# 09_LEDs_2.net
KiCad netlist of a schematic drawn in Altium Designer
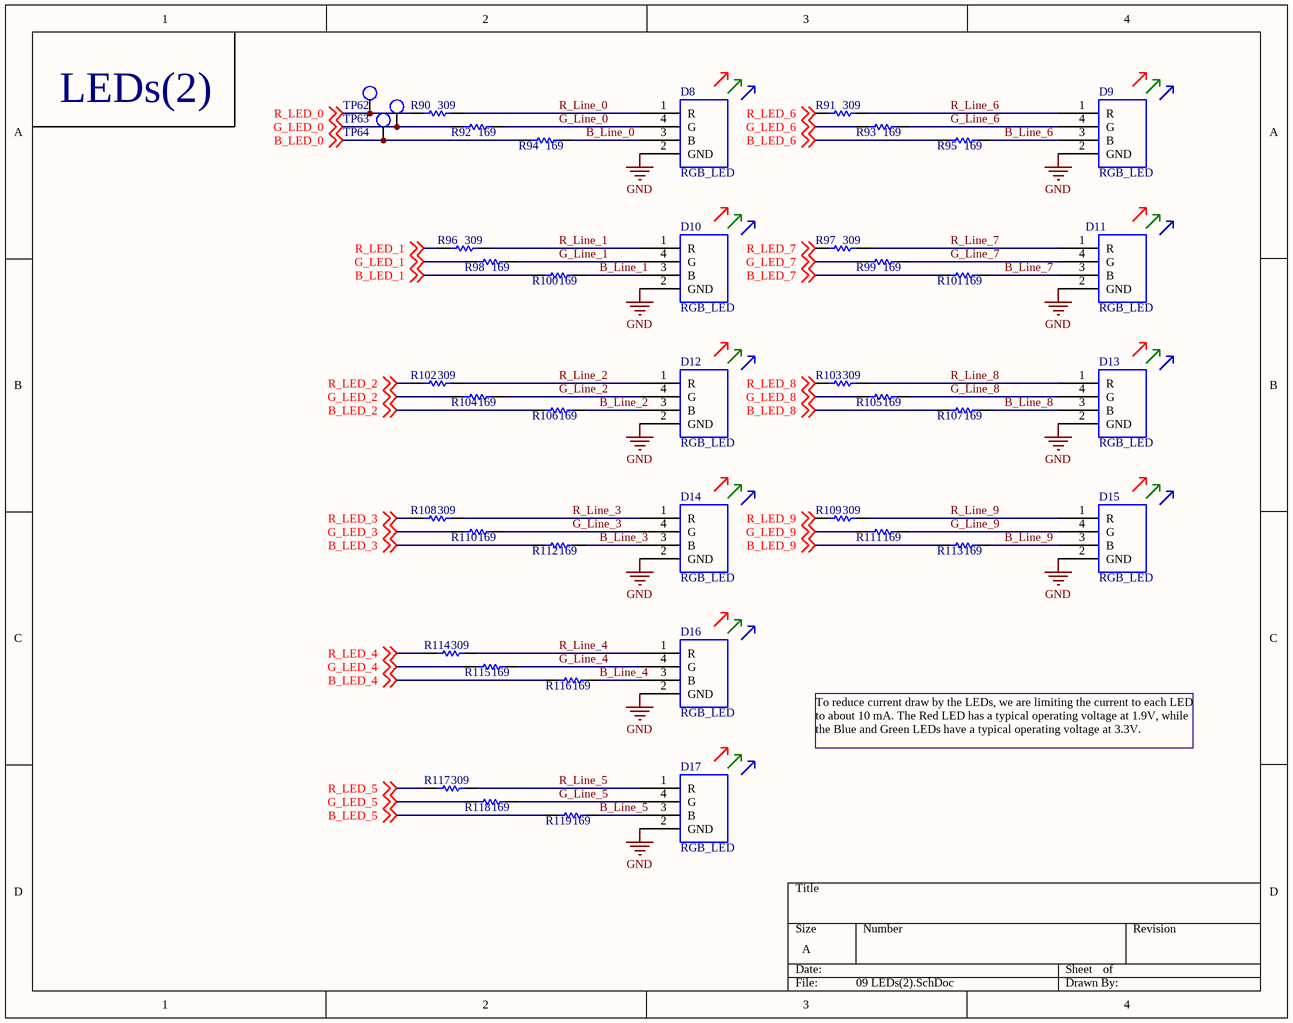
[diagram p0: 09 LEDs(2).SchDoc]

(export (version "E")
  (design (tool "Eeschema 10.0.6"))
  (components
    (comp (ref "D8")
      (value "RGB_LED")
      (footprint "RGB_LED")
      (description "WP154A4SUREQBFZGC")
      (fields (field (name "MANUFACTURER") "Kingbright"))
      (libsource (lib "schlib_truman") (part "RGB_LED"))
    )
    (comp (ref "D9")
      (value "RGB_LED")
      (footprint "RGB_LED")
      (description "WP154A4SUREQBFZGC")
      (fields (field (name "MANUFACTURER") "Kingbright"))
      (libsource (lib "schlib_truman") (part "RGB_LED"))
    )
    (comp (ref "D10")
      (value "RGB_LED")
      (footprint "RGB_LED")
      (description "WP154A4SUREQBFZGC")
      (fields (field (name "MANUFACTURER") "Kingbright"))
      (libsource (lib "schlib_truman") (part "RGB_LED"))
    )
    (comp (ref "D11")
      (value "RGB_LED")
      (footprint "RGB_LED")
      (description "WP154A4SUREQBFZGC")
      (fields (field (name "MANUFACTURER") "Kingbright"))
      (libsource (lib "schlib_truman") (part "RGB_LED"))
    )
    (comp (ref "D12")
      (value "RGB_LED")
      (footprint "RGB_LED")
      (description "WP154A4SUREQBFZGC")
      (fields (field (name "MANUFACTURER") "Kingbright"))
      (libsource (lib "schlib_truman") (part "RGB_LED"))
    )
    (comp (ref "D13")
      (value "RGB_LED")
      (footprint "RGB_LED")
      (description "WP154A4SUREQBFZGC")
      (fields (field (name "MANUFACTURER") "Kingbright"))
      (libsource (lib "schlib_truman") (part "RGB_LED"))
    )
    (comp (ref "D14")
      (value "RGB_LED")
      (footprint "RGB_LED")
      (description "WP154A4SUREQBFZGC")
      (fields (field (name "MANUFACTURER") "Kingbright"))
      (libsource (lib "schlib_truman") (part "RGB_LED"))
    )
    (comp (ref "D15")
      (value "RGB_LED")
      (footprint "RGB_LED")
      (description "WP154A4SUREQBFZGC")
      (fields (field (name "MANUFACTURER") "Kingbright"))
      (libsource (lib "schlib_truman") (part "RGB_LED"))
    )
    (comp (ref "D16")
      (value "RGB_LED")
      (footprint "RGB_LED")
      (description "WP154A4SUREQBFZGC")
      (fields (field (name "MANUFACTURER") "Kingbright"))
      (libsource (lib "schlib_truman") (part "RGB_LED"))
    )
    (comp (ref "D17")
      (value "RGB_LED")
      (footprint "RGB_LED")
      (description "WP154A4SUREQBFZGC")
      (fields (field (name "MANUFACTURER") "Kingbright"))
      (libsource (lib "schlib_truman") (part "RGB_LED"))
    )
    (comp (ref "R90")
      (value "RES_0805_309")
      (footprint "RES0805")
      (description "RES SMD 309 OHM 1% 1/8W 0805")
      (fields
        (field (name "MANUFACTURER") "Yageo")
        (field (name "MANUFACTURER PART NUMBER") "RC0805FR-07309RL")
        (field (name "ALTIUM_UNNAMED_1") "309")
      )
      (libsource (lib "schlib_truman") (part "RES_0805_309"))
    )
    (comp (ref "R91")
      (value "RES_0805_309")
      (footprint "RES0805")
      (description "RES SMD 309 OHM 1% 1/8W 0805")
      (fields
        (field (name "MANUFACTURER") "Yageo")
        (field (name "MANUFACTURER PART NUMBER") "RC0805FR-07309RL")
        (field (name "ALTIUM_UNNAMED_1") "309")
      )
      (libsource (lib "schlib_truman") (part "RES_0805_309"))
    )
    (comp (ref "R92")
      (value "169 Ohm")
      (footprint "RES0805")
      (description "RES SMD 169 OHM 1% 1/8W 0805")
      (fields
        (field (name "MANUFACTURER") "Yageo")
        (field (name "MANUFACTURER PART NUMBER") "RC0805FR-07169RL")
        (field (name "ALTIUM_UNNAMED_1") "169")
      )
      (libsource (lib "schlib_truman") (part "RES_0805_169"))
    )
    (comp (ref "R93")
      (value "169 Ohm")
      (footprint "RES0805")
      (description "RES SMD 169 OHM 1% 1/8W 0805")
      (fields
        (field (name "MANUFACTURER") "Yageo")
        (field (name "MANUFACTURER PART NUMBER") "RC0805FR-07169RL")
        (field (name "ALTIUM_UNNAMED_1") "169")
      )
      (libsource (lib "schlib_truman") (part "RES_0805_169"))
    )
    (comp (ref "R94")
      (value "169 Ohm")
      (footprint "RES0805")
      (description "RES SMD 169 OHM 1% 1/8W 0805")
      (fields
        (field (name "MANUFACTURER") "Yageo")
        (field (name "MANUFACTURER PART NUMBER") "RC0805FR-07169RL")
        (field (name "ALTIUM_UNNAMED_1") "169")
      )
      (libsource (lib "schlib_truman") (part "RES_0805_169"))
    )
    (comp (ref "R95")
      (value "169 Ohm")
      (footprint "RES0805")
      (description "RES SMD 169 OHM 1% 1/8W 0805")
      (fields
        (field (name "MANUFACTURER") "Yageo")
        (field (name "MANUFACTURER PART NUMBER") "RC0805FR-07169RL")
        (field (name "ALTIUM_UNNAMED_1") "169")
      )
      (libsource (lib "schlib_truman") (part "RES_0805_169"))
    )
    (comp (ref "R96")
      (value "RES_0805_309")
      (footprint "RES0805")
      (description "RES SMD 309 OHM 1% 1/8W 0805")
      (fields
        (field (name "MANUFACTURER") "Yageo")
        (field (name "MANUFACTURER PART NUMBER") "RC0805FR-07309RL")
        (field (name "ALTIUM_UNNAMED_1") "309")
      )
      (libsource (lib "schlib_truman") (part "RES_0805_309"))
    )
    (comp (ref "R97")
      (value "RES_0805_309")
      (footprint "RES0805")
      (description "RES SMD 309 OHM 1% 1/8W 0805")
      (fields
        (field (name "MANUFACTURER") "Yageo")
        (field (name "MANUFACTURER PART NUMBER") "RC0805FR-07309RL")
        (field (name "ALTIUM_UNNAMED_1") "309")
      )
      (libsource (lib "schlib_truman") (part "RES_0805_309"))
    )
    (comp (ref "R98")
      (value "169 Ohm")
      (footprint "RES0805")
      (description "RES SMD 169 OHM 1% 1/8W 0805")
      (fields
        (field (name "MANUFACTURER") "Yageo")
        (field (name "MANUFACTURER PART NUMBER") "RC0805FR-07169RL")
        (field (name "ALTIUM_UNNAMED_1") "169")
      )
      (libsource (lib "schlib_truman") (part "RES_0805_169"))
    )
    (comp (ref "R99")
      (value "169 Ohm")
      (footprint "RES0805")
      (description "RES SMD 169 OHM 1% 1/8W 0805")
      (fields
        (field (name "MANUFACTURER") "Yageo")
        (field (name "MANUFACTURER PART NUMBER") "RC0805FR-07169RL")
        (field (name "ALTIUM_UNNAMED_1") "169")
      )
      (libsource (lib "schlib_truman") (part "RES_0805_169"))
    )
    (comp (ref "R100")
      (value "169 Ohm")
      (footprint "RES0805")
      (description "RES SMD 169 OHM 1% 1/8W 0805")
      (fields
        (field (name "MANUFACTURER") "Yageo")
        (field (name "MANUFACTURER PART NUMBER") "RC0805FR-07169RL")
        (field (name "ALTIUM_UNNAMED_1") "169")
      )
      (libsource (lib "schlib_truman") (part "RES_0805_169"))
    )
    (comp (ref "R101")
      (value "169 Ohm")
      (footprint "RES0805")
      (description "RES SMD 169 OHM 1% 1/8W 0805")
      (fields
        (field (name "MANUFACTURER") "Yageo")
        (field (name "MANUFACTURER PART NUMBER") "RC0805FR-07169RL")
        (field (name "ALTIUM_UNNAMED_1") "169")
      )
      (libsource (lib "schlib_truman") (part "RES_0805_169"))
    )
    (comp (ref "R102")
      (value "RES_0805_309")
      (footprint "RES0805")
      (description "RES SMD 309 OHM 1% 1/8W 0805")
      (fields
        (field (name "MANUFACTURER") "Yageo")
        (field (name "MANUFACTURER PART NUMBER") "RC0805FR-07309RL")
        (field (name "ALTIUM_UNNAMED_1") "309")
      )
      (libsource (lib "schlib_truman") (part "RES_0805_309"))
    )
    (comp (ref "R103")
      (value "RES_0805_309")
      (footprint "RES0805")
      (description "RES SMD 309 OHM 1% 1/8W 0805")
      (fields
        (field (name "MANUFACTURER") "Yageo")
        (field (name "MANUFACTURER PART NUMBER") "RC0805FR-07309RL")
        (field (name "ALTIUM_UNNAMED_1") "309")
      )
      (libsource (lib "schlib_truman") (part "RES_0805_309"))
    )
    (comp (ref "R104")
      (value "169 Ohm")
      (footprint "RES0805")
      (description "RES SMD 169 OHM 1% 1/8W 0805")
      (fields
        (field (name "MANUFACTURER") "Yageo")
        (field (name "MANUFACTURER PART NUMBER") "RC0805FR-07169RL")
        (field (name "ALTIUM_UNNAMED_1") "169")
      )
      (libsource (lib "schlib_truman") (part "RES_0805_169"))
    )
    (comp (ref "R105")
      (value "169 Ohm")
      (footprint "RES0805")
      (description "RES SMD 169 OHM 1% 1/8W 0805")
      (fields
        (field (name "MANUFACTURER") "Yageo")
        (field (name "MANUFACTURER PART NUMBER") "RC0805FR-07169RL")
        (field (name "ALTIUM_UNNAMED_1") "169")
      )
      (libsource (lib "schlib_truman") (part "RES_0805_169"))
    )
    (comp (ref "R106")
      (value "169 Ohm")
      (footprint "RES0805")
      (description "RES SMD 169 OHM 1% 1/8W 0805")
      (fields
        (field (name "MANUFACTURER") "Yageo")
        (field (name "MANUFACTURER PART NUMBER") "RC0805FR-07169RL")
        (field (name "ALTIUM_UNNAMED_1") "169")
      )
      (libsource (lib "schlib_truman") (part "RES_0805_169"))
    )
    (comp (ref "R107")
      (value "169 Ohm")
      (footprint "RES0805")
      (description "RES SMD 169 OHM 1% 1/8W 0805")
      (fields
        (field (name "MANUFACTURER") "Yageo")
        (field (name "MANUFACTURER PART NUMBER") "RC0805FR-07169RL")
        (field (name "ALTIUM_UNNAMED_1") "169")
      )
      (libsource (lib "schlib_truman") (part "RES_0805_169"))
    )
    (comp (ref "R108")
      (value "RES_0805_309")
      (footprint "RES0805")
      (description "RES SMD 309 OHM 1% 1/8W 0805")
      (fields
        (field (name "MANUFACTURER") "Yageo")
        (field (name "MANUFACTURER PART NUMBER") "RC0805FR-07309RL")
        (field (name "ALTIUM_UNNAMED_1") "309")
      )
      (libsource (lib "schlib_truman") (part "RES_0805_309"))
    )
    (comp (ref "R109")
      (value "RES_0805_309")
      (footprint "RES0805")
      (description "RES SMD 309 OHM 1% 1/8W 0805")
      (fields
        (field (name "MANUFACTURER") "Yageo")
        (field (name "MANUFACTURER PART NUMBER") "RC0805FR-07309RL")
        (field (name "ALTIUM_UNNAMED_1") "309")
      )
      (libsource (lib "schlib_truman") (part "RES_0805_309"))
    )
    (comp (ref "R110")
      (value "169 Ohm")
      (footprint "RES0805")
      (description "RES SMD 169 OHM 1% 1/8W 0805")
      (fields
        (field (name "MANUFACTURER") "Yageo")
        (field (name "MANUFACTURER PART NUMBER") "RC0805FR-07169RL")
        (field (name "ALTIUM_UNNAMED_1") "169")
      )
      (libsource (lib "schlib_truman") (part "RES_0805_169"))
    )
    (comp (ref "R111")
      (value "169 Ohm")
      (footprint "RES0805")
      (description "RES SMD 169 OHM 1% 1/8W 0805")
      (fields
        (field (name "MANUFACTURER") "Yageo")
        (field (name "MANUFACTURER PART NUMBER") "RC0805FR-07169RL")
        (field (name "ALTIUM_UNNAMED_1") "169")
      )
      (libsource (lib "schlib_truman") (part "RES_0805_169"))
    )
    (comp (ref "R112")
      (value "169 Ohm")
      (footprint "RES0805")
      (description "RES SMD 169 OHM 1% 1/8W 0805")
      (fields
        (field (name "MANUFACTURER") "Yageo")
        (field (name "MANUFACTURER PART NUMBER") "RC0805FR-07169RL")
        (field (name "ALTIUM_UNNAMED_1") "169")
      )
      (libsource (lib "schlib_truman") (part "RES_0805_169"))
    )
    (comp (ref "R113")
      (value "169 Ohm")
      (footprint "RES0805")
      (description "RES SMD 169 OHM 1% 1/8W 0805")
      (fields
        (field (name "MANUFACTURER") "Yageo")
        (field (name "MANUFACTURER PART NUMBER") "RC0805FR-07169RL")
        (field (name "ALTIUM_UNNAMED_1") "169")
      )
      (libsource (lib "schlib_truman") (part "RES_0805_169"))
    )
    (comp (ref "R114")
      (value "RES_0805_309")
      (footprint "RES0805")
      (description "RES SMD 309 OHM 1% 1/8W 0805")
      (fields
        (field (name "MANUFACTURER") "Yageo")
        (field (name "MANUFACTURER PART NUMBER") "RC0805FR-07309RL")
        (field (name "ALTIUM_UNNAMED_1") "309")
      )
      (libsource (lib "schlib_truman") (part "RES_0805_309"))
    )
    (comp (ref "R115")
      (value "169 Ohm")
      (footprint "RES0805")
      (description "RES SMD 169 OHM 1% 1/8W 0805")
      (fields
        (field (name "MANUFACTURER") "Yageo")
        (field (name "MANUFACTURER PART NUMBER") "RC0805FR-07169RL")
        (field (name "ALTIUM_UNNAMED_1") "169")
      )
      (libsource (lib "schlib_truman") (part "RES_0805_169"))
    )
    (comp (ref "R116")
      (value "169 Ohm")
      (footprint "RES0805")
      (description "RES SMD 169 OHM 1% 1/8W 0805")
      (fields
        (field (name "MANUFACTURER") "Yageo")
        (field (name "MANUFACTURER PART NUMBER") "RC0805FR-07169RL")
        (field (name "ALTIUM_UNNAMED_1") "169")
      )
      (libsource (lib "schlib_truman") (part "RES_0805_169"))
    )
    (comp (ref "R117")
      (value "RES_0805_309")
      (footprint "RES0805")
      (description "RES SMD 309 OHM 1% 1/8W 0805")
      (fields
        (field (name "MANUFACTURER") "Yageo")
        (field (name "MANUFACTURER PART NUMBER") "RC0805FR-07309RL")
        (field (name "ALTIUM_UNNAMED_1") "309")
      )
      (libsource (lib "schlib_truman") (part "RES_0805_309"))
    )
    (comp (ref "R118")
      (value "169 Ohm")
      (footprint "RES0805")
      (description "RES SMD 169 OHM 1% 1/8W 0805")
      (fields
        (field (name "MANUFACTURER") "Yageo")
        (field (name "MANUFACTURER PART NUMBER") "RC0805FR-07169RL")
        (field (name "ALTIUM_UNNAMED_1") "169")
      )
      (libsource (lib "schlib_truman") (part "RES_0805_169"))
    )
    (comp (ref "R119")
      (value "169 Ohm")
      (footprint "RES0805")
      (description "RES SMD 169 OHM 1% 1/8W 0805")
      (fields
        (field (name "MANUFACTURER") "Yageo")
        (field (name "MANUFACTURER PART NUMBER") "RC0805FR-07169RL")
        (field (name "ALTIUM_UNNAMED_1") "169")
      )
      (libsource (lib "schlib_truman") (part "RES_0805_169"))
    )
    (comp (ref "TP62")
      (value "TP")
      (footprint "TestPoint_0805")
      (description "Testpoint_0805")
      (fields
        (field (name "MANUFACTURER") "TE Connectivity")
        (field (name "MANUFACTURER PART NUMBER") "1625854-2")
      )
      (libsource (lib "schlib_truman") (part "TP"))
    )
    (comp (ref "TP63")
      (value "TP")
      (footprint "TestPoint_0805")
      (description "Testpoint_0805")
      (fields
        (field (name "MANUFACTURER") "TE Connectivity")
        (field (name "MANUFACTURER PART NUMBER") "1625854-2")
      )
      (libsource (lib "schlib_truman") (part "TP"))
    )
    (comp (ref "TP64")
      (value "TP")
      (footprint "TestPoint_0805")
      (description "Testpoint_0805")
      (fields
        (field (name "MANUFACTURER") "TE Connectivity")
        (field (name "MANUFACTURER PART NUMBER") "1625854-2")
      )
      (libsource (lib "schlib_truman") (part "TP"))
    )
  )
  (nets
    (net (code "1") (name "/B_Line_0") (class "Default")
      (node (ref "D8") (pin "3") (pinfunction "B_3") (pintype "passive"))
      (node (ref "R94") (pin "2") (pinfunction "2_2") (pintype "passive"))
    )
    (net (code "2") (name "/B_Line_1") (class "Default")
      (node (ref "D10") (pin "3") (pinfunction "B_3") (pintype "passive"))
      (node (ref "R100") (pin "2") (pinfunction "2_2") (pintype "passive"))
    )
    (net (code "3") (name "/B_Line_2") (class "Default")
      (node (ref "D12") (pin "3") (pinfunction "B_3") (pintype "passive"))
      (node (ref "R106") (pin "2") (pinfunction "2_2") (pintype "passive"))
    )
    (net (code "4") (name "/B_Line_3") (class "Default")
      (node (ref "D14") (pin "3") (pinfunction "B_3") (pintype "passive"))
      (node (ref "R112") (pin "2") (pinfunction "2_2") (pintype "passive"))
    )
    (net (code "5") (name "/B_Line_4") (class "Default")
      (node (ref "D16") (pin "3") (pinfunction "B_3") (pintype "passive"))
      (node (ref "R116") (pin "2") (pinfunction "2_2") (pintype "passive"))
    )
    (net (code "6") (name "/B_Line_5") (class "Default")
      (node (ref "D17") (pin "3") (pinfunction "B_3") (pintype "passive"))
      (node (ref "R119") (pin "2") (pinfunction "2_2") (pintype "passive"))
    )
    (net (code "7") (name "/B_Line_6") (class "Default")
      (node (ref "D9") (pin "3") (pinfunction "B_3") (pintype "passive"))
      (node (ref "R95") (pin "2") (pinfunction "2_2") (pintype "passive"))
    )
    (net (code "8") (name "/B_Line_7") (class "Default")
      (node (ref "D11") (pin "3") (pinfunction "B_3") (pintype "passive"))
      (node (ref "R101") (pin "2") (pinfunction "2_2") (pintype "passive"))
    )
    (net (code "9") (name "/B_Line_8") (class "Default")
      (node (ref "D13") (pin "3") (pinfunction "B_3") (pintype "passive"))
      (node (ref "R107") (pin "2") (pinfunction "2_2") (pintype "passive"))
    )
    (net (code "10") (name "/B_Line_9") (class "Default")
      (node (ref "D15") (pin "3") (pinfunction "B_3") (pintype "passive"))
      (node (ref "R113") (pin "2") (pinfunction "2_2") (pintype "passive"))
    )
    (net (code "11") (name "/G_Line_0") (class "Default")
      (node (ref "D8") (pin "4") (pinfunction "G_4") (pintype "passive"))
      (node (ref "R92") (pin "2") (pinfunction "2_2") (pintype "passive"))
    )
    (net (code "12") (name "/G_Line_1") (class "Default")
      (node (ref "D10") (pin "4") (pinfunction "G_4") (pintype "passive"))
      (node (ref "R98") (pin "2") (pinfunction "2_2") (pintype "passive"))
    )
    (net (code "13") (name "/G_Line_2") (class "Default")
      (node (ref "D12") (pin "4") (pinfunction "G_4") (pintype "passive"))
      (node (ref "R104") (pin "2") (pinfunction "2_2") (pintype "passive"))
    )
    (net (code "14") (name "/G_Line_3") (class "Default")
      (node (ref "D14") (pin "4") (pinfunction "G_4") (pintype "passive"))
      (node (ref "R110") (pin "2") (pinfunction "2_2") (pintype "passive"))
    )
    (net (code "15") (name "/G_Line_4") (class "Default")
      (node (ref "D16") (pin "4") (pinfunction "G_4") (pintype "passive"))
      (node (ref "R115") (pin "2") (pinfunction "2_2") (pintype "passive"))
    )
    (net (code "16") (name "/G_Line_5") (class "Default")
      (node (ref "D17") (pin "4") (pinfunction "G_4") (pintype "passive"))
      (node (ref "R118") (pin "2") (pinfunction "2_2") (pintype "passive"))
    )
    (net (code "17") (name "/G_Line_6") (class "Default")
      (node (ref "D9") (pin "4") (pinfunction "G_4") (pintype "passive"))
      (node (ref "R93") (pin "2") (pinfunction "2_2") (pintype "passive"))
    )
    (net (code "18") (name "/G_Line_7") (class "Default")
      (node (ref "D11") (pin "4") (pinfunction "G_4") (pintype "passive"))
      (node (ref "R99") (pin "2") (pinfunction "2_2") (pintype "passive"))
    )
    (net (code "19") (name "/G_Line_8") (class "Default")
      (node (ref "D13") (pin "4") (pinfunction "G_4") (pintype "passive"))
      (node (ref "R105") (pin "2") (pinfunction "2_2") (pintype "passive"))
    )
    (net (code "20") (name "/G_Line_9") (class "Default")
      (node (ref "D15") (pin "4") (pinfunction "G_4") (pintype "passive"))
      (node (ref "R111") (pin "2") (pinfunction "2_2") (pintype "passive"))
    )
    (net (code "21") (name "/R_Line_0") (class "Default")
      (node (ref "D8") (pin "1") (pinfunction "R_1") (pintype "passive"))
      (node (ref "R90") (pin "2") (pinfunction "2_2") (pintype "passive"))
    )
    (net (code "22") (name "/R_Line_1") (class "Default")
      (node (ref "D10") (pin "1") (pinfunction "R_1") (pintype "passive"))
      (node (ref "R96") (pin "2") (pinfunction "2_2") (pintype "passive"))
    )
    (net (code "23") (name "/R_Line_2") (class "Default")
      (node (ref "D12") (pin "1") (pinfunction "R_1") (pintype "passive"))
      (node (ref "R102") (pin "2") (pinfunction "2_2") (pintype "passive"))
    )
    (net (code "24") (name "/R_Line_3") (class "Default")
      (node (ref "D14") (pin "1") (pinfunction "R_1") (pintype "passive"))
      (node (ref "R108") (pin "2") (pinfunction "2_2") (pintype "passive"))
    )
    (net (code "25") (name "/R_Line_4") (class "Default")
      (node (ref "D16") (pin "1") (pinfunction "R_1") (pintype "passive"))
      (node (ref "R114") (pin "2") (pinfunction "2_2") (pintype "passive"))
    )
    (net (code "26") (name "/R_Line_5") (class "Default")
      (node (ref "D17") (pin "1") (pinfunction "R_1") (pintype "passive"))
      (node (ref "R117") (pin "2") (pinfunction "2_2") (pintype "passive"))
    )
    (net (code "27") (name "/R_Line_6") (class "Default")
      (node (ref "D9") (pin "1") (pinfunction "R_1") (pintype "passive"))
      (node (ref "R91") (pin "2") (pinfunction "2_2") (pintype "passive"))
    )
    (net (code "28") (name "/R_Line_7") (class "Default")
      (node (ref "D11") (pin "1") (pinfunction "R_1") (pintype "passive"))
      (node (ref "R97") (pin "2") (pinfunction "2_2") (pintype "passive"))
    )
    (net (code "29") (name "/R_Line_8") (class "Default")
      (node (ref "D13") (pin "1") (pinfunction "R_1") (pintype "passive"))
      (node (ref "R103") (pin "2") (pinfunction "2_2") (pintype "passive"))
    )
    (net (code "30") (name "/R_Line_9") (class "Default")
      (node (ref "D15") (pin "1") (pinfunction "R_1") (pintype "passive"))
      (node (ref "R109") (pin "2") (pinfunction "2_2") (pintype "passive"))
    )
    (net (code "31") (name "B_LED_0") (class "Default")
      (node (ref "R94") (pin "1") (pinfunction "1_1") (pintype "passive"))
      (node (ref "TP64") (pin "1") (pintype "passive"))
    )
    (net (code "32") (name "B_LED_1") (class "Default")
      (node (ref "R100") (pin "1") (pinfunction "1_1") (pintype "passive"))
    )
    (net (code "33") (name "B_LED_2") (class "Default")
      (node (ref "R106") (pin "1") (pinfunction "1_1") (pintype "passive"))
    )
    (net (code "34") (name "B_LED_3") (class "Default")
      (node (ref "R112") (pin "1") (pinfunction "1_1") (pintype "passive"))
    )
    (net (code "35") (name "B_LED_4") (class "Default")
      (node (ref "R116") (pin "1") (pinfunction "1_1") (pintype "passive"))
    )
    (net (code "36") (name "B_LED_5") (class "Default")
      (node (ref "R119") (pin "1") (pinfunction "1_1") (pintype "passive"))
    )
    (net (code "37") (name "B_LED_6") (class "Default")
      (node (ref "R95") (pin "1") (pinfunction "1_1") (pintype "passive"))
    )
    (net (code "38") (name "B_LED_7") (class "Default")
      (node (ref "R101") (pin "1") (pinfunction "1_1") (pintype "passive"))
    )
    (net (code "39") (name "B_LED_8") (class "Default")
      (node (ref "R107") (pin "1") (pinfunction "1_1") (pintype "passive"))
    )
    (net (code "40") (name "B_LED_9") (class "Default")
      (node (ref "R113") (pin "1") (pinfunction "1_1") (pintype "passive"))
    )
    (net (code "41") (name "GND") (class "Default")
      (node (ref "D10") (pin "2") (pinfunction "GND_2") (pintype "power_in"))
      (node (ref "D11") (pin "2") (pinfunction "GND_2") (pintype "power_in"))
      (node (ref "D12") (pin "2") (pinfunction "GND_2") (pintype "power_in"))
      (node (ref "D13") (pin "2") (pinfunction "GND_2") (pintype "power_in"))
      (node (ref "D14") (pin "2") (pinfunction "GND_2") (pintype "power_in"))
      (node (ref "D15") (pin "2") (pinfunction "GND_2") (pintype "power_in"))
      (node (ref "D16") (pin "2") (pinfunction "GND_2") (pintype "power_in"))
      (node (ref "D17") (pin "2") (pinfunction "GND_2") (pintype "power_in"))
      (node (ref "D8") (pin "2") (pinfunction "GND_2") (pintype "power_in"))
      (node (ref "D9") (pin "2") (pinfunction "GND_2") (pintype "power_in"))
    )
    (net (code "42") (name "G_LED_0") (class "Default")
      (node (ref "R92") (pin "1") (pinfunction "1_1") (pintype "passive"))
      (node (ref "TP63") (pin "1") (pintype "passive"))
    )
    (net (code "43") (name "G_LED_1") (class "Default")
      (node (ref "R98") (pin "1") (pinfunction "1_1") (pintype "passive"))
    )
    (net (code "44") (name "G_LED_2") (class "Default")
      (node (ref "R104") (pin "1") (pinfunction "1_1") (pintype "passive"))
    )
    (net (code "45") (name "G_LED_3") (class "Default")
      (node (ref "R110") (pin "1") (pinfunction "1_1") (pintype "passive"))
    )
    (net (code "46") (name "G_LED_4") (class "Default")
      (node (ref "R115") (pin "1") (pinfunction "1_1") (pintype "passive"))
    )
    (net (code "47") (name "G_LED_5") (class "Default")
      (node (ref "R118") (pin "1") (pinfunction "1_1") (pintype "passive"))
    )
    (net (code "48") (name "G_LED_6") (class "Default")
      (node (ref "R93") (pin "1") (pinfunction "1_1") (pintype "passive"))
    )
    (net (code "49") (name "G_LED_7") (class "Default")
      (node (ref "R99") (pin "1") (pinfunction "1_1") (pintype "passive"))
    )
    (net (code "50") (name "G_LED_8") (class "Default")
      (node (ref "R105") (pin "1") (pinfunction "1_1") (pintype "passive"))
    )
    (net (code "51") (name "G_LED_9") (class "Default")
      (node (ref "R111") (pin "1") (pinfunction "1_1") (pintype "passive"))
    )
    (net (code "52") (name "R_LED_0") (class "Default")
      (node (ref "R90") (pin "1") (pinfunction "1_1") (pintype "passive"))
      (node (ref "TP62") (pin "1") (pintype "passive"))
    )
    (net (code "53") (name "R_LED_1") (class "Default")
      (node (ref "R96") (pin "1") (pinfunction "1_1") (pintype "passive"))
    )
    (net (code "54") (name "R_LED_2") (class "Default")
      (node (ref "R102") (pin "1") (pinfunction "1_1") (pintype "passive"))
    )
    (net (code "55") (name "R_LED_3") (class "Default")
      (node (ref "R108") (pin "1") (pinfunction "1_1") (pintype "passive"))
    )
    (net (code "56") (name "R_LED_4") (class "Default")
      (node (ref "R114") (pin "1") (pinfunction "1_1") (pintype "passive"))
    )
    (net (code "57") (name "R_LED_5") (class "Default")
      (node (ref "R117") (pin "1") (pinfunction "1_1") (pintype "passive"))
    )
    (net (code "58") (name "R_LED_6") (class "Default")
      (node (ref "R91") (pin "1") (pinfunction "1_1") (pintype "passive"))
    )
    (net (code "59") (name "R_LED_7") (class "Default")
      (node (ref "R97") (pin "1") (pinfunction "1_1") (pintype "passive"))
    )
    (net (code "60") (name "R_LED_8") (class "Default")
      (node (ref "R103") (pin "1") (pinfunction "1_1") (pintype "passive"))
    )
    (net (code "61") (name "R_LED_9") (class "Default")
      (node (ref "R109") (pin "1") (pinfunction "1_1") (pintype "passive"))
    )
  )
)
